# Sheet_sanya.net
KiCad netlist of a schematic drawn in Altium Designer
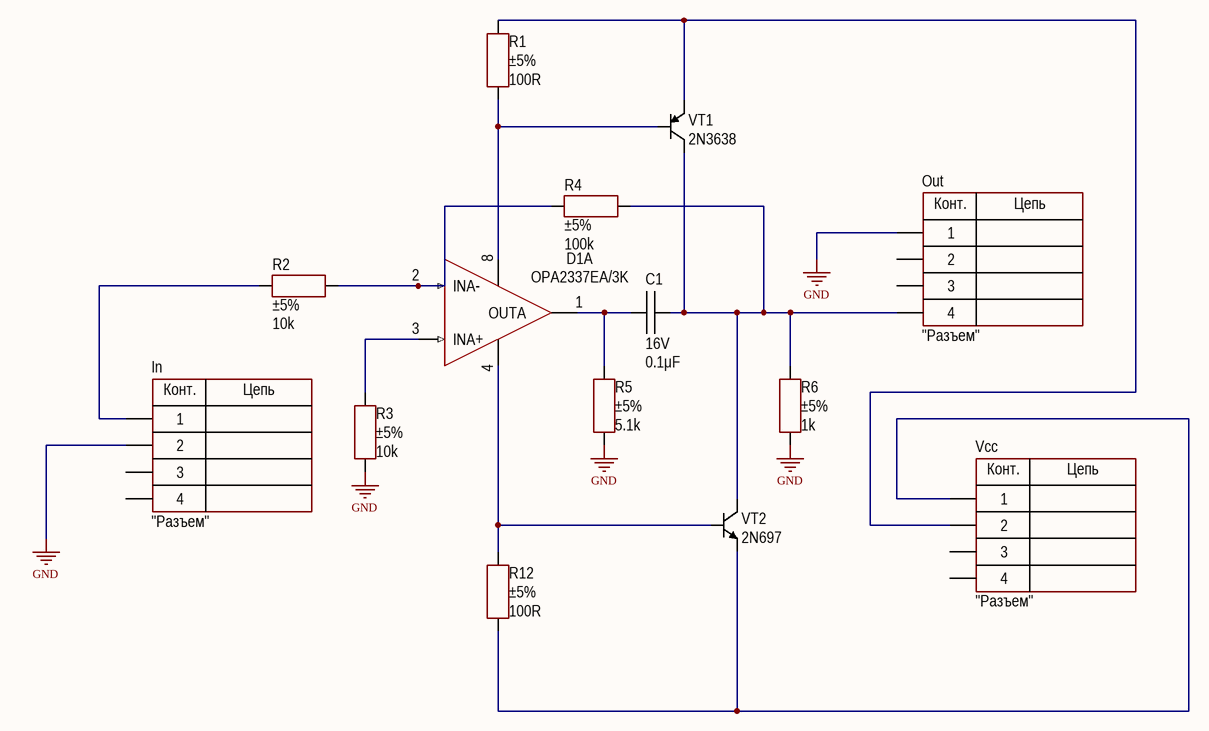
[diagram p0: Sheet(sanya).SchDoc]

(export (version "E")
  (design (tool "Eeschema 10.0.6"))
  (components
    (comp (ref "C1")
      (value "0.1μF")
      (footprint "CAP: 0201")
      (fields
        (field (name "MANUFACTURER") "Yageo")
        (field (name "PARTNUMBER") "CC0201KRX7R7BB103")
        (field (name "VALUEMANUFACTURERPARTNUMBER") "Ceramic capacitor, 0.1μF, X7R, ±10%, 16V, 0201, -55...+125°C")
        (field (name "VOLTAGE") "16V")
      )
      (libsource (lib "Capacitor") (part "Ceramic_0201"))
    )
    (comp (ref "D1")
      (value "~")
      (footprint "SOT23-8")
      (description "OP amplifier")
      (fields
        (field (name "MANUFACTURER") "Texas Instruments")
        (field (name "VALUEMANUFACTURERPARTNUMBER") "IC op amplifier, Rail-to-Rail, 3 MHz, 2.7...5.5V, -40...+125°C, SOT23-5")
        (field (name "PARTNUMBER") "OPA2337EA/3K")
      )
      (libsource (lib "IC. Amplifier") (part "OPA2337EA/3K"))
    )
    (comp (ref "In")
      (value "~")
      (footprint "CON: SM04B-GHS")
      (fields
        (field (name "MANUFACTURER") "JST")
        (field (name "VALUEMANUFACTURERPARTNUMBER") "Connector, 4pin, 1.25mm, 50VDC, 1A")
        (field (name "PARTNUMBER") "SM04B-GHS")
        (field (name "COMMENTTEXT") "\"Разъем\"")
      )
      (libsource (lib "Connector") (part "Connector_SM04B"))
    )
    (comp (ref "Out")
      (value "~")
      (footprint "CON: SM04B-GHS")
      (fields
        (field (name "MANUFACTURER") "JST")
        (field (name "VALUEMANUFACTURERPARTNUMBER") "Connector, 4pin, 1.25mm, 50VDC, 1A")
        (field (name "PARTNUMBER") "SM04B-GHS")
        (field (name "COMMENTTEXT") "\"Разъем\"")
      )
      (libsource (lib "Connector") (part "Connector_SM04B"))
    )
    (comp (ref "R1")
      (value "100R")
      (footprint "RES: 0402")
      (fields
        (field (name "MANUFACTURER") "Yageo")
        (field (name "PARTNUMBER") "RC0402JR-07100RL")
        (field (name "VALUEMANUFACTURERPARTNUMBER") "Resistor film, 100R, ±5%, 0402, 0.063W, -55...+125°C")
        (field (name "TOLERANCE") "±5%")
      )
      (libsource (lib "") (part "Resistor_0402_1"))
    )
    (comp (ref "R2")
      (value "10k")
      (footprint "RES: 0402")
      (fields
        (field (name "MANUFACTURER") "Yageo")
        (field (name "PARTNUMBER") "RC0402JR-07100RL")
        (field (name "VALUEMANUFACTURERPARTNUMBER") "Resistor film, 10k, ±5%, 0402, 0.063W, -55...+125°C")
        (field (name "TOLERANCE") "±5%")
      )
      (libsource (lib "") (part "Resistor_0402_3"))
    )
    (comp (ref "R3")
      (value "10k")
      (footprint "RES: 0402")
      (fields
        (field (name "MANUFACTURER") "Yageo")
        (field (name "PARTNUMBER") "RC0402JR-07100RL")
        (field (name "VALUEMANUFACTURERPARTNUMBER") "Resistor film, 10k, ±5%, 0402, 0.063W, -55...+125°C")
        (field (name "TOLERANCE") "±5%")
      )
      (libsource (lib "") (part "Resistor_0402_1"))
    )
    (comp (ref "R4")
      (value "100k")
      (footprint "RES: 0402")
      (fields
        (field (name "MANUFACTURER") "Yageo")
        (field (name "PARTNUMBER") "RC0402JR-07100RL")
        (field (name "VALUEMANUFACTURERPARTNUMBER") "Resistor film, 100k, ±5%, 0402, 0.063W, -55...+125°C")
        (field (name "TOLERANCE") "±5%")
      )
      (libsource (lib "Resistor") (part "Resistor_0402"))
    )
    (comp (ref "R5")
      (value "5.1k")
      (footprint "RES: 0402")
      (fields
        (field (name "MANUFACTURER") "Yageo")
        (field (name "PARTNUMBER") "RC0402JR-07100RL")
        (field (name "VALUEMANUFACTURERPARTNUMBER") "Resistor film, 5.1k, ±5%, 0402, 0.063W, -55...+125°C")
        (field (name "TOLERANCE") "±5%")
      )
      (libsource (lib "") (part "Resistor_0402_2"))
    )
    (comp (ref "R6")
      (value "1k")
      (footprint "RES: 0402")
      (fields
        (field (name "MANUFACTURER") "Yageo")
        (field (name "PARTNUMBER") "RC0402JR-07100RL")
        (field (name "VALUEMANUFACTURERPARTNUMBER") "Resistor film, 1k, ±5%, 0402, 0.063W, -55...+125°C")
        (field (name "TOLERANCE") "±5%")
      )
      (libsource (lib "") (part "Resistor_0402_2"))
    )
    (comp (ref "R12")
      (value "100R")
      (footprint "RES: 0402")
      (fields
        (field (name "MANUFACTURER") "Yageo")
        (field (name "PARTNUMBER") "RC0402JR-07100RL")
        (field (name "VALUEMANUFACTURERPARTNUMBER") "Resistor film, 100R, ±5%, 0402, 0.063W, -55...+125°C")
        (field (name "TOLERANCE") "±5%")
      )
      (libsource (lib "") (part "Resistor_0402_2"))
    )
    (comp (ref "Vcc")
      (value "~")
      (footprint "CON: SM04B-GHS")
      (fields
        (field (name "MANUFACTURER") "JST")
        (field (name "VALUEMANUFACTURERPARTNUMBER") "Connector, 4pin, 1.25mm, 50VDC, 1A")
        (field (name "PARTNUMBER") "SM04B-GHS")
        (field (name "COMMENTTEXT") "\"Разъем\"")
      )
      (libsource (lib "Connector") (part "Connector_SM04B"))
    )
    (comp (ref "VT1")
      (value "~")
      (footprint "SOT23")
      (fields
        (field (name "MANUFACTURER") "ON Semiconductor")
        (field (name "VALUEMANUFACTURERPARTNUMBER") "PNP transistor, 45V, 100mA, 100MHz, 300mW, 0.65V, 220, SOT-23, -55...+125°C")
        (field (name "PARTNUMBER") "2N3638")
      )
      (libsource (lib "Transistor") (part "BJT_PNP_132"))
    )
    (comp (ref "VT2")
      (value "~")
      (footprint "SOT23")
      (fields
        (field (name "MANUFACTURER") "ON Semiconductor")
        (field (name "VALUEMANUFACTURERPARTNUMBER") "NPN transistor, 45V, 100mA, 100MHz, 300mW, 0.6V, 420, SOT-23, -55...+125°C")
        (field (name "PARTNUMBER") "2N697")
      )
      (libsource (lib "Transistor") (part "BJT_NPN_123"))
    )
  )
  (nets
    (net (code "1") (name "GND") (class "Default")
      (node (ref "In") (pin "2") (pinfunction "2_2") (pintype "passive"))
      (node (ref "Out") (pin "1") (pinfunction "1_1") (pintype "passive"))
      (node (ref "R3") (pin "1") (pinfunction "1_1") (pintype "passive"))
      (node (ref "R5") (pin "2") (pinfunction "2_2") (pintype "passive"))
      (node (ref "R6") (pin "2") (pinfunction "2_2") (pintype "passive"))
    )
    (net (code "2") (name "Net-(D1A-INA+)") (class "Default")
      (node (ref "D1") (pin "3") (pinfunction "INA+_3") (pintype "input"))
      (node (ref "R3") (pin "2") (pinfunction "2_2") (pintype "passive"))
    )
    (net (code "3") (name "Net-(D1A-INA-)") (class "Default")
      (node (ref "D1") (pin "2") (pinfunction "INA-_2") (pintype "input"))
      (node (ref "R2") (pin "2") (pinfunction "2_2") (pintype "passive"))
      (node (ref "R4") (pin "2") (pinfunction "2_2") (pintype "passive"))
    )
    (net (code "4") (name "Net-(D1A-OUTA)") (class "Default")
      (node (ref "C1") (pin "2") (pinfunction "2_2") (pintype "power_in"))
      (node (ref "D1") (pin "1") (pinfunction "OUTA_1") (pintype "power_in"))
      (node (ref "R5") (pin "1") (pinfunction "1_1") (pintype "passive"))
    )
    (net (code "5") (name "Net-(D1A-V+)") (class "Default")
      (node (ref "D1") (pin "8") (pinfunction "V+_8") (pintype "power_in"))
      (node (ref "R1") (pin "1") (pinfunction "1_1") (pintype "passive"))
      (node (ref "VT1") (pin "1") (pinfunction "B_1") (pintype "passive"))
    )
    (net (code "6") (name "Net-(D1A-V-)") (class "Default")
      (node (ref "D1") (pin "4") (pinfunction "V-_4") (pintype "power_in"))
      (node (ref "R12") (pin "1") (pinfunction "1_1") (pintype "passive"))
      (node (ref "VT2") (pin "1") (pinfunction "B_1") (pintype "passive"))
    )
    (net (code "7") (name "Net-(In-Pad1)") (class "Default")
      (node (ref "In") (pin "1") (pinfunction "1_1") (pintype "passive"))
      (node (ref "R2") (pin "1") (pinfunction "1_1") (pintype "passive"))
    )
    (net (code "8") (name "Net-(VT1-C)") (class "Default")
      (node (ref "C1") (pin "1") (pinfunction "1_1") (pintype "power_in"))
      (node (ref "Out") (pin "4") (pinfunction "4_4") (pintype "power_in"))
      (node (ref "R4") (pin "1") (pinfunction "1_1") (pintype "passive"))
      (node (ref "R6") (pin "1") (pinfunction "1_1") (pintype "passive"))
      (node (ref "VT1") (pin "2") (pinfunction "C_2") (pintype "passive"))
      (node (ref "VT2") (pin "2") (pinfunction "C_2") (pintype "passive"))
    )
    (net (code "9") (name "Net-(VT1-E)") (class "Default")
      (node (ref "R1") (pin "2") (pinfunction "2_2") (pintype "passive"))
      (node (ref "VT1") (pin "3") (pinfunction "E_3") (pintype "passive"))
      (node (ref "Vcc") (pin "2") (pinfunction "2_2") (pintype "passive"))
    )
    (net (code "10") (name "Net-(VT2-E)") (class "Default")
      (node (ref "R12") (pin "2") (pinfunction "2_2") (pintype "passive"))
      (node (ref "VT2") (pin "3") (pinfunction "E_3") (pintype "passive"))
      (node (ref "Vcc") (pin "1") (pinfunction "1_1") (pintype "passive"))
    )
    (net (code "11") (name "unconnected-(In-Pad3)") (class "Default")
      (node (ref "In") (pin "3") (pinfunction "3_3") (pintype "power_in"))
    )
    (net (code "12") (name "unconnected-(In-Pad4)") (class "Default")
      (node (ref "In") (pin "4") (pinfunction "4_4") (pintype "power_in"))
    )
    (net (code "13") (name "unconnected-(Out-Pad2)") (class "Default")
      (node (ref "Out") (pin "2") (pinfunction "2_2") (pintype "passive"))
    )
    (net (code "14") (name "unconnected-(Out-Pad3)") (class "Default")
      (node (ref "Out") (pin "3") (pinfunction "3_3") (pintype "power_in"))
    )
    (net (code "15") (name "unconnected-(Vcc-Pad3)") (class "Default")
      (node (ref "Vcc") (pin "3") (pinfunction "3_3") (pintype "power_in"))
    )
    (net (code "16") (name "unconnected-(Vcc-Pad4)") (class "Default")
      (node (ref "Vcc") (pin "4") (pinfunction "4_4") (pintype "power_in"))
    )
  )
)
